# BSU_EADC.net
KiCad netlist of a schematic drawn in Altium Designer
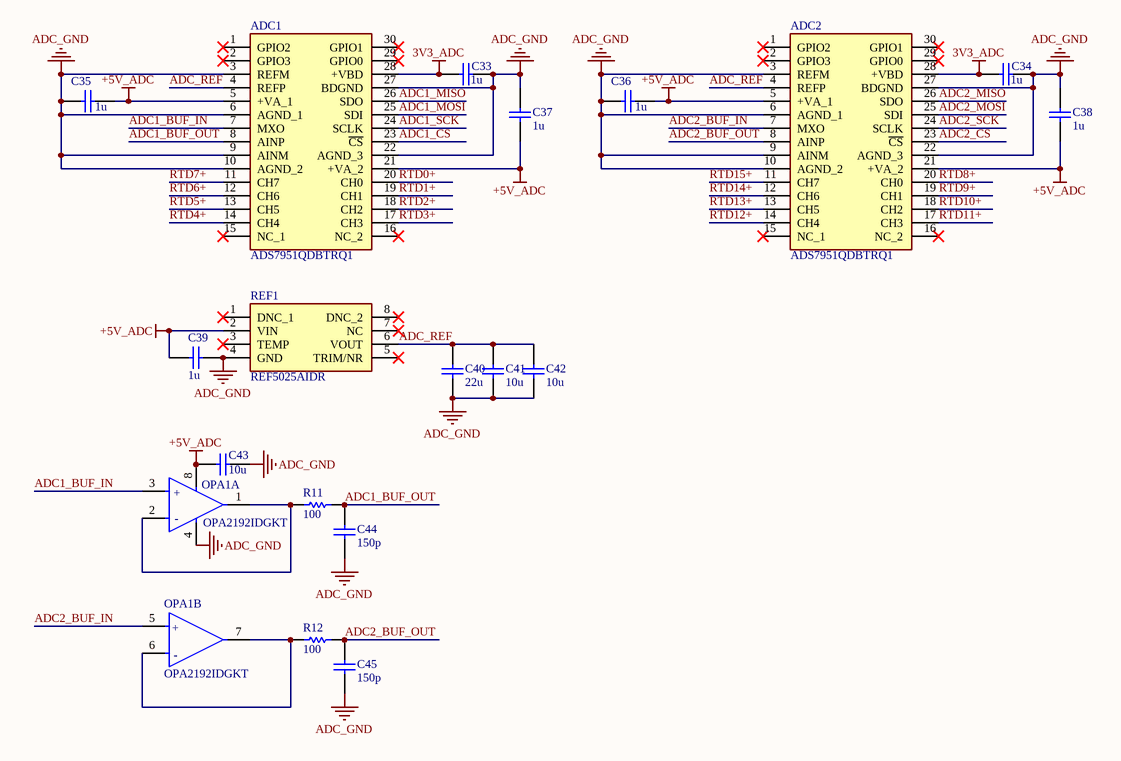
[diagram p0: BSU_EADC.SchDoc]

(export (version "E")
  (design (tool "Eeschema 10.0.6"))
  (components
    (comp (ref "ADC1")
      (value "ADS7951QDBTRQ1")
      (footprint "TSSOP30_ADS7951")
      (description "Automotive 12 bit, 1 MSPS, 8 Channel, Single-Ended, SAR ADC")
      (fields (field (name "MOUSER PART NUMBER") "595-ADS7951QDBTRQ1"))
      (libsource (lib "BMS_ShareComponentLibrary") (part "ADS7951QDBTRQ1"))
    )
    (comp (ref "ADC2")
      (value "ADS7951QDBTRQ1")
      (footprint "TSSOP30_ADS7951")
      (description "Automotive 12 bit, 1 MSPS, 8 Channel, Single-Ended, SAR ADC")
      (fields (field (name "MOUSER PART NUMBER") "595-ADS7951QDBTRQ1"))
      (libsource (lib "BMS_ShareComponentLibrary") (part "ADS7951QDBTRQ1"))
    )
    (comp (ref "C33")
      (value "1u")
      (footprint "0805_SMD_C")
      (description "0805 SMD Capacitor")
      (libsource (lib "BMS_ShareComponentLibrary") (part "0805_SMD_Capacitor"))
    )
    (comp (ref "C34")
      (value "1u")
      (footprint "0805_SMD_C")
      (description "0805 SMD Capacitor")
      (libsource (lib "BMS_ShareComponentLibrary") (part "0805_SMD_Capacitor"))
    )
    (comp (ref "C35")
      (value "1u")
      (footprint "0805_SMD_C")
      (description "0805 SMD Capacitor")
      (libsource (lib "BMS_ShareComponentLibrary") (part "0805_SMD_Capacitor"))
    )
    (comp (ref "C36")
      (value "1u")
      (footprint "0805_SMD_C")
      (description "0805 SMD Capacitor")
      (libsource (lib "BMS_ShareComponentLibrary") (part "0805_SMD_Capacitor"))
    )
    (comp (ref "C37")
      (value "1u")
      (footprint "0805_SMD_C")
      (description "0805 SMD Capacitor")
      (libsource (lib "BMS_ShareComponentLibrary") (part "0805_SMD_Capacitor"))
    )
    (comp (ref "C38")
      (value "1u")
      (footprint "0805_SMD_C")
      (description "0805 SMD Capacitor")
      (libsource (lib "BMS_ShareComponentLibrary") (part "0805_SMD_Capacitor"))
    )
    (comp (ref "C39")
      (value "1u")
      (footprint "0805_SMD_C")
      (description "0805 SMD Capacitor")
      (libsource (lib "BMS_ShareComponentLibrary") (part "0805_SMD_Capacitor"))
    )
    (comp (ref "C40")
      (value "22u")
      (footprint "0805_SMD_C")
      (description "0805 SMD Capacitor")
      (libsource (lib "BMS_ShareComponentLibrary") (part "0805_SMD_Capacitor"))
    )
    (comp (ref "C41")
      (value "10u")
      (footprint "0805_SMD_C")
      (description "0805 SMD Capacitor")
      (libsource (lib "BMS_ShareComponentLibrary") (part "0805_SMD_Capacitor"))
    )
    (comp (ref "C42")
      (value "10u")
      (footprint "0805_SMD_C")
      (description "0805 SMD Capacitor")
      (libsource (lib "BMS_ShareComponentLibrary") (part "0805_SMD_Capacitor"))
    )
    (comp (ref "C43")
      (value "10u")
      (footprint "0805_SMD_C")
      (description "0805 SMD Capacitor")
      (libsource (lib "BMS_ShareComponentLibrary") (part "0805_SMD_Capacitor"))
    )
    (comp (ref "C44")
      (value "150p")
      (footprint "0805_SMD_C")
      (description "0805 SMD Capacitor")
      (libsource (lib "BMS_ShareComponentLibrary") (part "0805_SMD_Capacitor"))
    )
    (comp (ref "C45")
      (value "150p")
      (footprint "0805_SMD_C")
      (description "0805 SMD Capacitor")
      (libsource (lib "BMS_ShareComponentLibrary") (part "0805_SMD_Capacitor"))
    )
    (comp (ref "OPA1")
      (value "OPA2192IDGKT")
      (footprint "VSSOP8_OPA2192")
      (description "36-V, Precision, RRIO, Low Offset Voltage, Low Input Bias Current Op Amp With e-trim")
      (fields (field (name "MOUSER PART NUMBER") "595-OPA2192IDGKT"))
      (libsource (lib "BMS_ShareComponentLibrary") (part "OPA2192IDGKT"))
    )
    (comp (ref "R11")
      (value "100")
      (footprint "0805_SMD_R")
      (description "0805 SMD Resistor")
      (libsource (lib "BMS_ShareComponentLibrary") (part "0805_SMD_Resistor"))
    )
    (comp (ref "R12")
      (value "100")
      (footprint "0805_SMD_R")
      (description "0805 SMD Resistor")
      (libsource (lib "BMS_ShareComponentLibrary") (part "0805_SMD_Resistor"))
    )
    (comp (ref "REF1")
      (value "REF5025AIDR")
      (footprint "SOIC8_REF5025")
      (description "3 Vpp/V Noise, 3 ppm/C Drift Precision Series Voltage Reference")
      (fields (field (name "MOUSER PART NUMBER") "595-REF5025AIDR"))
      (libsource (lib "BMS_ShareComponentLibrary") (part "REF5025AIDR"))
    )
  )
  (nets
    (net (code "1") (name "+5V_ADC") (class "Default")
      (node (ref "ADC1") (pin "21") (pinfunction "+VA_2_21") (pintype "passive"))
      (node (ref "ADC1") (pin "5") (pinfunction "+VA_1_5") (pintype "passive"))
      (node (ref "ADC2") (pin "21") (pinfunction "+VA_2_21") (pintype "passive"))
      (node (ref "ADC2") (pin "5") (pinfunction "+VA_1_5") (pintype "passive"))
      (node (ref "C35") (pin "1") (pinfunction "1_1") (pintype "passive"))
      (node (ref "C36") (pin "1") (pinfunction "1_1") (pintype "passive"))
      (node (ref "C37") (pin "2") (pinfunction "2_2") (pintype "passive"))
      (node (ref "C38") (pin "2") (pinfunction "2_2") (pintype "passive"))
      (node (ref "C39") (pin "1") (pinfunction "1_1") (pintype "passive"))
      (node (ref "C43") (pin "2") (pinfunction "2_2") (pintype "passive"))
      (node (ref "OPA1") (pin "8") (pinfunction "VDD_8") (pintype "power_in"))
      (node (ref "REF1") (pin "2") (pinfunction "VIN_2") (pintype "passive"))
    )
    (net (code "2") (name "/ADC1_BUF_IN") (class "Default")
      (node (ref "ADC1") (pin "7") (pinfunction "MXO_7") (pintype "passive"))
      (node (ref "OPA1") (pin "3") (pinfunction "1IN+_3") (pintype "tri_state"))
    )
    (net (code "3") (name "/ADC1_BUF_OUT") (class "Default")
      (node (ref "ADC1") (pin "8") (pinfunction "AINP_8") (pintype "passive"))
      (node (ref "C44") (pin "2") (pinfunction "2_2") (pintype "passive"))
      (node (ref "R11") (pin "2") (pinfunction "2_2") (pintype "passive"))
    )
    (net (code "4") (name "/ADC1_CS") (class "Default")
      (node (ref "ADC1") (pin "23") (pinfunction "~{CS}_23") (pintype "passive"))
    )
    (net (code "5") (name "/ADC1_MISO") (class "Default")
      (node (ref "ADC1") (pin "26") (pinfunction "SDO_26") (pintype "passive"))
    )
    (net (code "6") (name "/ADC1_MOSI") (class "Default")
      (node (ref "ADC1") (pin "25") (pinfunction "SDI_25") (pintype "passive"))
    )
    (net (code "7") (name "/ADC1_SCK") (class "Default")
      (node (ref "ADC1") (pin "24") (pinfunction "SCLK_24") (pintype "passive"))
    )
    (net (code "8") (name "/ADC2_BUF_IN") (class "Default")
      (node (ref "ADC2") (pin "7") (pinfunction "MXO_7") (pintype "passive"))
      (node (ref "OPA1") (pin "5") (pinfunction "2IN+_5") (pintype "tri_state"))
    )
    (net (code "9") (name "/ADC2_BUF_OUT") (class "Default")
      (node (ref "ADC2") (pin "8") (pinfunction "AINP_8") (pintype "passive"))
      (node (ref "C45") (pin "2") (pinfunction "2_2") (pintype "passive"))
      (node (ref "R12") (pin "2") (pinfunction "2_2") (pintype "passive"))
    )
    (net (code "10") (name "/ADC2_CS") (class "Default")
      (node (ref "ADC2") (pin "23") (pinfunction "~{CS}_23") (pintype "passive"))
    )
    (net (code "11") (name "/ADC2_MISO") (class "Default")
      (node (ref "ADC2") (pin "26") (pinfunction "SDO_26") (pintype "passive"))
    )
    (net (code "12") (name "/ADC2_MOSI") (class "Default")
      (node (ref "ADC2") (pin "25") (pinfunction "SDI_25") (pintype "passive"))
    )
    (net (code "13") (name "/ADC2_SCK") (class "Default")
      (node (ref "ADC2") (pin "24") (pinfunction "SCLK_24") (pintype "passive"))
    )
    (net (code "14") (name "/ADC_REF") (class "Default")
      (node (ref "ADC1") (pin "4") (pinfunction "REFP_4") (pintype "passive"))
      (node (ref "ADC2") (pin "4") (pinfunction "REFP_4") (pintype "passive"))
      (node (ref "C40") (pin "2") (pinfunction "2_2") (pintype "passive"))
      (node (ref "C41") (pin "2") (pinfunction "2_2") (pintype "passive"))
      (node (ref "C42") (pin "2") (pinfunction "2_2") (pintype "passive"))
      (node (ref "REF1") (pin "6") (pinfunction "VOUT_6") (pintype "passive"))
    )
    (net (code "15") (name "/RTD0+") (class "Default")
      (node (ref "ADC1") (pin "20") (pinfunction "CH0_20") (pintype "passive"))
    )
    (net (code "16") (name "/RTD1+") (class "Default")
      (node (ref "ADC1") (pin "19") (pinfunction "CH1_19") (pintype "passive"))
    )
    (net (code "17") (name "/RTD2+") (class "Default")
      (node (ref "ADC1") (pin "18") (pinfunction "CH2_18") (pintype "passive"))
    )
    (net (code "18") (name "/RTD3+") (class "Default")
      (node (ref "ADC1") (pin "17") (pinfunction "CH3_17") (pintype "passive"))
    )
    (net (code "19") (name "/RTD4+") (class "Default")
      (node (ref "ADC1") (pin "14") (pinfunction "CH4_14") (pintype "passive"))
    )
    (net (code "20") (name "/RTD5+") (class "Default")
      (node (ref "ADC1") (pin "13") (pinfunction "CH5_13") (pintype "passive"))
    )
    (net (code "21") (name "/RTD6+") (class "Default")
      (node (ref "ADC1") (pin "12") (pinfunction "CH6_12") (pintype "passive"))
    )
    (net (code "22") (name "/RTD7+") (class "Default")
      (node (ref "ADC1") (pin "11") (pinfunction "CH7_11") (pintype "passive"))
    )
    (net (code "23") (name "/RTD8+") (class "Default")
      (node (ref "ADC2") (pin "20") (pinfunction "CH0_20") (pintype "passive"))
    )
    (net (code "24") (name "/RTD9+") (class "Default")
      (node (ref "ADC2") (pin "19") (pinfunction "CH1_19") (pintype "passive"))
    )
    (net (code "25") (name "/RTD10+") (class "Default")
      (node (ref "ADC2") (pin "18") (pinfunction "CH2_18") (pintype "passive"))
    )
    (net (code "26") (name "/RTD11+") (class "Default")
      (node (ref "ADC2") (pin "17") (pinfunction "CH3_17") (pintype "passive"))
    )
    (net (code "27") (name "/RTD12+") (class "Default")
      (node (ref "ADC2") (pin "14") (pinfunction "CH4_14") (pintype "passive"))
    )
    (net (code "28") (name "/RTD13+") (class "Default")
      (node (ref "ADC2") (pin "13") (pinfunction "CH5_13") (pintype "passive"))
    )
    (net (code "29") (name "/RTD14+") (class "Default")
      (node (ref "ADC2") (pin "12") (pinfunction "CH6_12") (pintype "passive"))
    )
    (net (code "30") (name "/RTD15+") (class "Default")
      (node (ref "ADC2") (pin "11") (pinfunction "CH7_11") (pintype "passive"))
    )
    (net (code "31") (name "3V3_ADC") (class "Default")
      (node (ref "ADC1") (pin "28") (pinfunction "+VBD_28") (pintype "passive"))
      (node (ref "ADC2") (pin "28") (pinfunction "+VBD_28") (pintype "passive"))
      (node (ref "C33") (pin "1") (pinfunction "1_1") (pintype "passive"))
      (node (ref "C34") (pin "1") (pinfunction "1_1") (pintype "passive"))
    )
    (net (code "32") (name "ADC_GND") (class "Default")
      (node (ref "ADC1") (pin "10") (pinfunction "AGND_2_10") (pintype "passive"))
      (node (ref "ADC1") (pin "22") (pinfunction "AGND_3_22") (pintype "passive"))
      (node (ref "ADC1") (pin "27") (pinfunction "BDGND_27") (pintype "passive"))
      (node (ref "ADC1") (pin "3") (pinfunction "REFM_3") (pintype "passive"))
      (node (ref "ADC1") (pin "6") (pinfunction "AGND_1_6") (pintype "passive"))
      (node (ref "ADC1") (pin "9") (pinfunction "AINM_9") (pintype "passive"))
      (node (ref "ADC2") (pin "10") (pinfunction "AGND_2_10") (pintype "passive"))
      (node (ref "ADC2") (pin "22") (pinfunction "AGND_3_22") (pintype "passive"))
      (node (ref "ADC2") (pin "27") (pinfunction "BDGND_27") (pintype "passive"))
      (node (ref "ADC2") (pin "3") (pinfunction "REFM_3") (pintype "passive"))
      (node (ref "ADC2") (pin "6") (pinfunction "AGND_1_6") (pintype "passive"))
      (node (ref "ADC2") (pin "9") (pinfunction "AINM_9") (pintype "passive"))
      (node (ref "C33") (pin "2") (pinfunction "2_2") (pintype "passive"))
      (node (ref "C34") (pin "2") (pinfunction "2_2") (pintype "passive"))
      (node (ref "C35") (pin "2") (pinfunction "2_2") (pintype "passive"))
      (node (ref "C36") (pin "2") (pinfunction "2_2") (pintype "passive"))
      (node (ref "C37") (pin "1") (pinfunction "1_1") (pintype "passive"))
      (node (ref "C38") (pin "1") (pinfunction "1_1") (pintype "passive"))
      (node (ref "C39") (pin "2") (pinfunction "2_2") (pintype "passive"))
      (node (ref "C40") (pin "1") (pinfunction "1_1") (pintype "passive"))
      (node (ref "C41") (pin "1") (pinfunction "1_1") (pintype "passive"))
      (node (ref "C42") (pin "1") (pinfunction "1_1") (pintype "passive"))
      (node (ref "C43") (pin "1") (pinfunction "1_1") (pintype "passive"))
      (node (ref "C44") (pin "1") (pinfunction "1_1") (pintype "passive"))
      (node (ref "C45") (pin "1") (pinfunction "1_1") (pintype "passive"))
      (node (ref "OPA1") (pin "4") (pinfunction "GND_4") (pintype "power_in"))
      (node (ref "REF1") (pin "4") (pinfunction "GND_4") (pintype "passive"))
    )
    (net (code "33") (name "Net-(OPA1A-1IN-)") (class "Default")
      (node (ref "OPA1") (pin "1") (pinfunction "1OUT_1") (pintype "passive"))
      (node (ref "OPA1") (pin "2") (pinfunction "1IN-_2") (pintype "tri_state"))
      (node (ref "R11") (pin "1") (pinfunction "1_1") (pintype "passive"))
    )
    (net (code "34") (name "Net-(OPA1B-2IN-)") (class "Default")
      (node (ref "OPA1") (pin "6") (pinfunction "2IN-_6") (pintype "tri_state"))
      (node (ref "OPA1") (pin "7") (pinfunction "2OUT_7") (pintype "passive"))
      (node (ref "R12") (pin "1") (pinfunction "1_1") (pintype "passive"))
    )
    (net (code "35") (name "unconnected-(ADC1-GPIO0-Pad29)") (class "Default")
      (node (ref "ADC1") (pin "29") (pinfunction "GPIO0_29") (pintype "passive+no_connect"))
    )
    (net (code "36") (name "unconnected-(ADC1-GPIO1-Pad30)") (class "Default")
      (node (ref "ADC1") (pin "30") (pinfunction "GPIO1_30") (pintype "passive+no_connect"))
    )
    (net (code "37") (name "unconnected-(ADC1-GPIO2-Pad1)") (class "Default")
      (node (ref "ADC1") (pin "1") (pinfunction "GPIO2_1") (pintype "passive+no_connect"))
    )
    (net (code "38") (name "unconnected-(ADC1-GPIO3-Pad2)") (class "Default")
      (node (ref "ADC1") (pin "2") (pinfunction "GPIO3_2") (pintype "passive+no_connect"))
    )
    (net (code "39") (name "unconnected-(ADC1-NC_1-Pad15)") (class "Default")
      (node (ref "ADC1") (pin "15") (pinfunction "NC_1_15") (pintype "passive+no_connect"))
    )
    (net (code "40") (name "unconnected-(ADC1-NC_2-Pad16)") (class "Default")
      (node (ref "ADC1") (pin "16") (pinfunction "NC_2_16") (pintype "passive+no_connect"))
    )
    (net (code "41") (name "unconnected-(ADC2-GPIO0-Pad29)") (class "Default")
      (node (ref "ADC2") (pin "29") (pinfunction "GPIO0_29") (pintype "passive+no_connect"))
    )
    (net (code "42") (name "unconnected-(ADC2-GPIO1-Pad30)") (class "Default")
      (node (ref "ADC2") (pin "30") (pinfunction "GPIO1_30") (pintype "passive+no_connect"))
    )
    (net (code "43") (name "unconnected-(ADC2-GPIO2-Pad1)") (class "Default")
      (node (ref "ADC2") (pin "1") (pinfunction "GPIO2_1") (pintype "passive+no_connect"))
    )
    (net (code "44") (name "unconnected-(ADC2-GPIO3-Pad2)") (class "Default")
      (node (ref "ADC2") (pin "2") (pinfunction "GPIO3_2") (pintype "passive+no_connect"))
    )
    (net (code "45") (name "unconnected-(ADC2-NC_1-Pad15)") (class "Default")
      (node (ref "ADC2") (pin "15") (pinfunction "NC_1_15") (pintype "passive+no_connect"))
    )
    (net (code "46") (name "unconnected-(ADC2-NC_2-Pad16)") (class "Default")
      (node (ref "ADC2") (pin "16") (pinfunction "NC_2_16") (pintype "passive+no_connect"))
    )
    (net (code "47") (name "unconnected-(REF1-DNC_1-Pad1)") (class "Default")
      (node (ref "REF1") (pin "1") (pinfunction "DNC_1_1") (pintype "passive+no_connect"))
    )
    (net (code "48") (name "unconnected-(REF1-DNC_2-Pad8)") (class "Default")
      (node (ref "REF1") (pin "8") (pinfunction "DNC_2_8") (pintype "passive+no_connect"))
    )
    (net (code "49") (name "unconnected-(REF1-NC-Pad7)") (class "Default")
      (node (ref "REF1") (pin "7") (pinfunction "NC_7") (pintype "passive+no_connect"))
    )
    (net (code "50") (name "unconnected-(REF1-TEMP-Pad3)") (class "Default")
      (node (ref "REF1") (pin "3") (pinfunction "TEMP_3") (pintype "passive+no_connect"))
    )
    (net (code "51") (name "unconnected-(REF1-TRIM{slash}NR-Pad5)") (class "Default")
      (node (ref "REF1") (pin "5") (pinfunction "TRIM/NR_5") (pintype "passive+no_connect"))
    )
  )
)
